# BATT_CONNECTOR.net
KiCad netlist of a schematic drawn in EAGLE
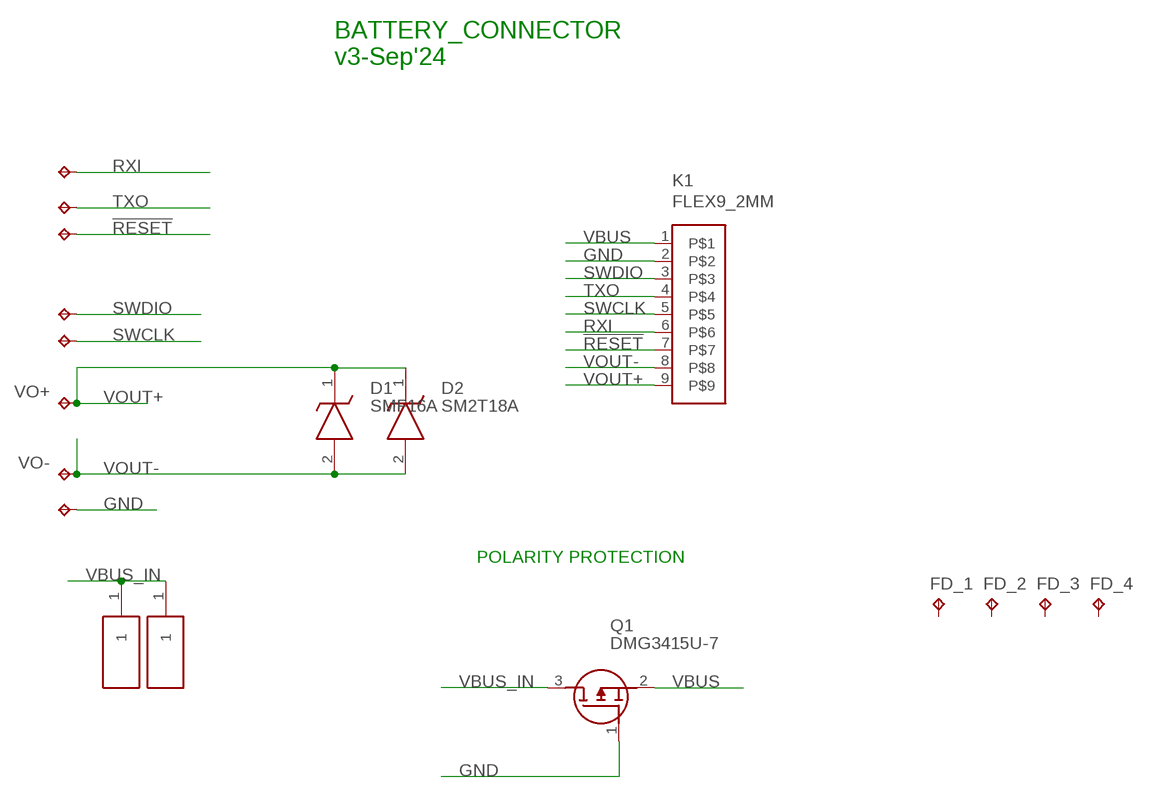
[diagram p0: schematic, sheet 1]

(export (version "E")
  (design (tool "Eeschema 10.0.6"))
  (components
    (comp (ref "!RESET")
      (value "TPB2,54")
      (footprint "eagle-import:B2,54")
      (libsource (lib "eagle-import") (part "TPB2,54"))
    )
    (comp (ref "D1")
      (value "SMF16A")
      (footprint "eagle-import:SODFL3618X110N")
      (fields (field (name "MOUSER_PART_NUMBER") "576-SMF16A"))
      (libsource (lib "eagle-import") (part "SMF16A"))
    )
    (comp (ref "D2")
      (value "SM2T18A")
      (footprint "eagle-import:SM2T18A")
      (fields (field (name "MOUSER_PART_NUMBER") "511-SM2T18A"))
      (libsource (lib "eagle-import") (part "SM2T18A"))
    )
    (comp (ref "FD_1")
      (value "FD_1")
      (footprint "eagle-import:TP06SQ")
      (libsource (lib "eagle-import") (part "TPTP06SQ"))
    )
    (comp (ref "FD_2")
      (value "FD_1")
      (footprint "eagle-import:TP06SQ")
      (libsource (lib "eagle-import") (part "TPTP06SQ"))
    )
    (comp (ref "FD_3")
      (value "FD_1")
      (footprint "eagle-import:TP06SQ")
      (libsource (lib "eagle-import") (part "TPTP06SQ"))
    )
    (comp (ref "FD_4")
      (value "FD_1")
      (footprint "eagle-import:TP06SQ")
      (libsource (lib "eagle-import") (part "TPTP06SQ"))
    )
    (comp (ref "GND")
      (value "TPB2,54")
      (footprint "eagle-import:B2,54")
      (libsource (lib "eagle-import") (part "TPB2,54"))
    )
    (comp (ref "H1")
      (value "S1761-42R")
      (footprint "eagle-import:S176142R")
      (fields (field (name "MOUSER_PART_NUMBER") "855-S1761-42R"))
      (libsource (lib "eagle-import") (part "S1761-42R"))
    )
    (comp (ref "H2")
      (value "S1761-42R")
      (footprint "eagle-import:S176142R")
      (fields (field (name "MOUSER_PART_NUMBER") "855-S1761-42R"))
      (libsource (lib "eagle-import") (part "S1761-42R"))
    )
    (comp (ref "K1")
      (value "FLEX9_2MM")
      (footprint "eagle-import:FLEX9_2MM")
      (libsource (lib "eagle-import") (part "FLEX9_2MM"))
    )
    (comp (ref "Q1")
      (value "DMG3415U-7")
      (footprint "eagle-import:SSM3J332RLFT")
      (fields
        (field (name "ARROW_PART_NUMBER") "SSM3J338R,LF")
        (field (name "MOUSER_PART_NUMBER") "757-SSM3J338RLF")
      )
      (libsource (lib "eagle-import") (part "SSM3J338R,LF"))
    )
    (comp (ref "RXI")
      (value "TPB2,54")
      (footprint "eagle-import:B2,54")
      (libsource (lib "eagle-import") (part "TPB2,54"))
    )
    (comp (ref "SWCLK")
      (value "TPB2,54")
      (footprint "eagle-import:B2,54")
      (libsource (lib "eagle-import") (part "TPB2,54"))
    )
    (comp (ref "SWDIO")
      (value "TPB2,54")
      (footprint "eagle-import:B2,54")
      (libsource (lib "eagle-import") (part "TPB2,54"))
    )
    (comp (ref "TXO")
      (value "TPB2,54")
      (footprint "eagle-import:B2,54")
      (libsource (lib "eagle-import") (part "TPB2,54"))
    )
    (comp (ref "VO+")
      (value "TPB2,54")
      (footprint "eagle-import:B2,54")
      (libsource (lib "eagle-import") (part "TPB2,54"))
    )
    (comp (ref "VO-")
      (value "TPB2,54")
      (footprint "eagle-import:B2,54")
      (libsource (lib "eagle-import") (part "TPB2,54"))
    )
  )
  (nets
    (net (code "1") (name "/GND") (class "Default")
      (node (ref "GND") (pin "TP") (pinfunction "TP_TP") (pintype "input"))
      (node (ref "K1") (pin "2") (pinfunction "P$2_2") (pintype "bidirectional"))
      (node (ref "Q1") (pin "1") (pinfunction "G_1") (pintype "bidirectional"))
    )
    (net (code "2") (name "/RXI") (class "Default")
      (node (ref "K1") (pin "6") (pinfunction "P$6_6") (pintype "bidirectional"))
      (node (ref "RXI") (pin "TP") (pinfunction "TP_TP") (pintype "input"))
    )
    (net (code "3") (name "/SWCLK") (class "Default")
      (node (ref "K1") (pin "5") (pinfunction "P$5_5") (pintype "bidirectional"))
      (node (ref "SWCLK") (pin "TP") (pinfunction "TP_TP") (pintype "input"))
    )
    (net (code "4") (name "/SWDIO") (class "Default")
      (node (ref "K1") (pin "3") (pinfunction "P$3_3") (pintype "bidirectional"))
      (node (ref "SWDIO") (pin "TP") (pinfunction "TP_TP") (pintype "input"))
    )
    (net (code "5") (name "/TXO") (class "Default")
      (node (ref "K1") (pin "4") (pinfunction "P$4_4") (pintype "bidirectional"))
      (node (ref "TXO") (pin "TP") (pinfunction "TP_TP") (pintype "input"))
    )
    (net (code "6") (name "/VBUS") (class "Default")
      (node (ref "K1") (pin "1") (pinfunction "P$1_1") (pintype "bidirectional"))
      (node (ref "Q1") (pin "2") (pinfunction "S_2") (pintype "bidirectional"))
    )
    (net (code "7") (name "/VBUS_IN") (class "Default")
      (node (ref "H1") (pin "1") (pinfunction "1_1") (pintype "bidirectional"))
      (node (ref "H2") (pin "1") (pinfunction "1_1") (pintype "bidirectional"))
      (node (ref "Q1") (pin "3") (pinfunction "D_3") (pintype "bidirectional"))
    )
    (net (code "8") (name "/VOUT+") (class "Default")
      (node (ref "D1") (pin "1") (pinfunction "K_1") (pintype "bidirectional"))
      (node (ref "D2") (pin "1") (pinfunction "K_1") (pintype "bidirectional"))
      (node (ref "K1") (pin "9") (pinfunction "P$9_9") (pintype "bidirectional"))
      (node (ref "VO+") (pin "TP") (pinfunction "TP_TP") (pintype "input"))
    )
    (net (code "9") (name "/VOUT-") (class "Default")
      (node (ref "D1") (pin "2") (pinfunction "A_2") (pintype "bidirectional"))
      (node (ref "D2") (pin "2") (pinfunction "A_2") (pintype "bidirectional"))
      (node (ref "K1") (pin "8") (pinfunction "P$8_8") (pintype "bidirectional"))
      (node (ref "VO-") (pin "TP") (pinfunction "TP_TP") (pintype "input"))
    )
    (net (code "10") (name "/~{RESET}") (class "Default")
      (node (ref "!RESET") (pin "TP") (pinfunction "TP_TP") (pintype "input"))
      (node (ref "K1") (pin "7") (pinfunction "P$7_7") (pintype "bidirectional"))
    )
    (net (code "11") (name "unconnected-(FD_1-PadTP)") (class "Default")
      (node (ref "FD_1") (pin "TP") (pinfunction "TP_TP") (pintype "input"))
    )
    (net (code "12") (name "unconnected-(FD_2-PadTP)") (class "Default")
      (node (ref "FD_2") (pin "TP") (pinfunction "TP_TP") (pintype "input"))
    )
    (net (code "13") (name "unconnected-(FD_3-PadTP)") (class "Default")
      (node (ref "FD_3") (pin "TP") (pinfunction "TP_TP") (pintype "input"))
    )
    (net (code "14") (name "unconnected-(FD_4-PadTP)") (class "Default")
      (node (ref "FD_4") (pin "TP") (pinfunction "TP_TP") (pintype "input"))
    )
  )
)
